# CubeSatBoard1.net
KiCad netlist of a schematic drawn in EAGLE
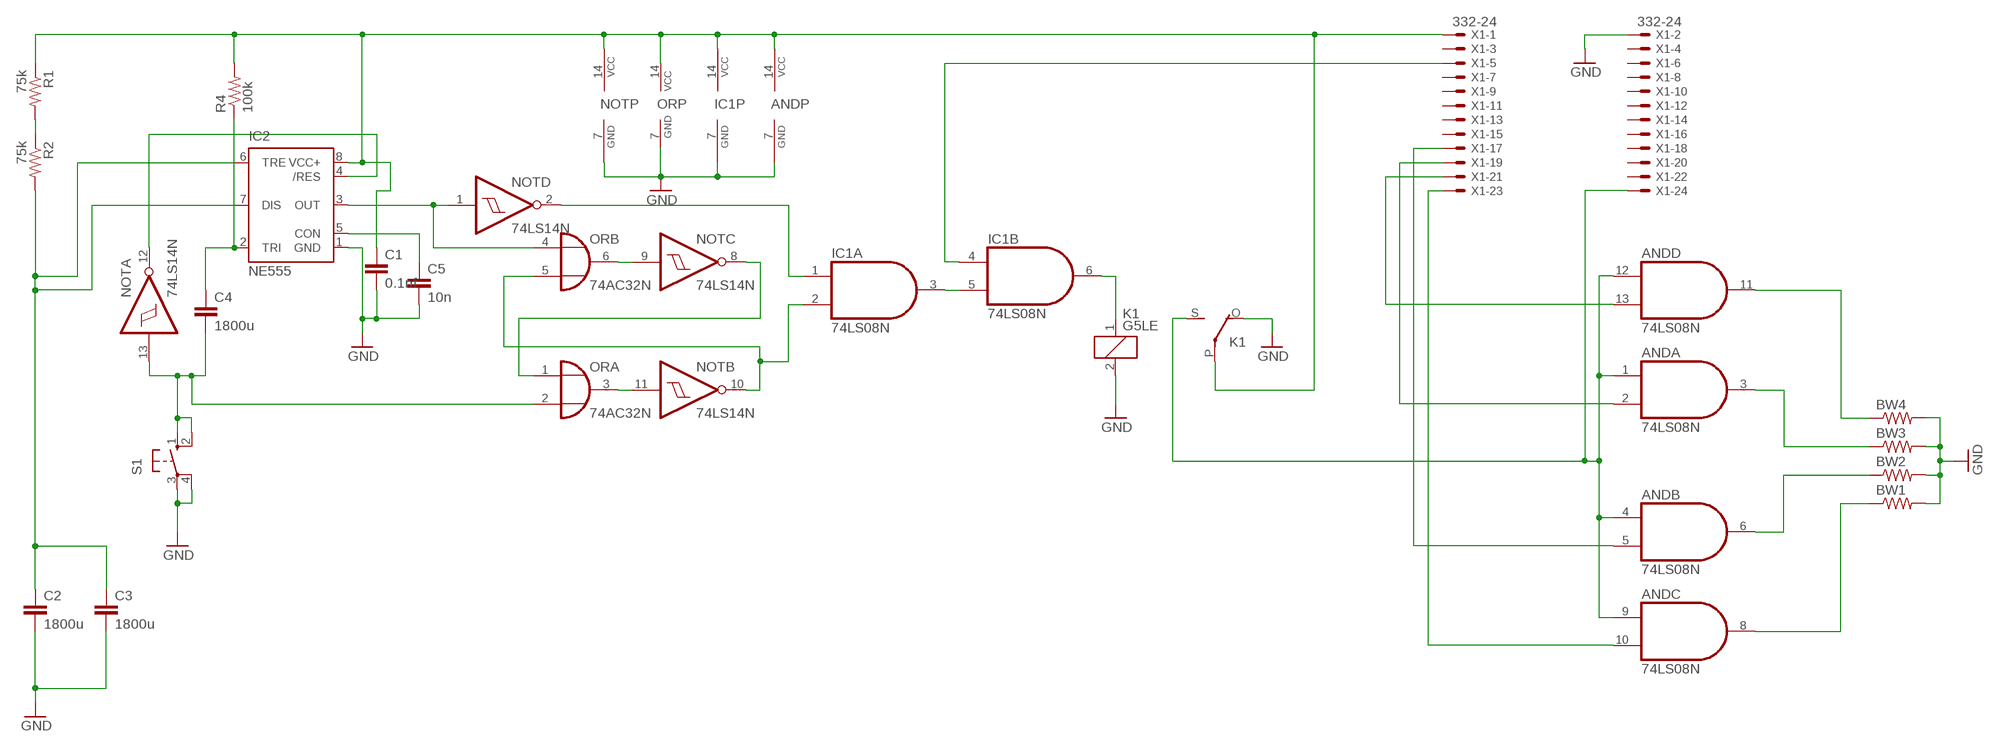
[diagram p0: schematic, sheet 1]

(export (version "E")
  (design (tool "Eeschema 10.0.6"))
  (components
    (comp (ref "AND")
      (value "74LS08N")
      (footprint "eagle-import:DIL14")
      (libsource (lib "eagle-import") (part "7408NLS"))
    )
    (comp (ref "BW1")
      (value "R-US_0309/10")
      (footprint "eagle-import:0309_10")
      (libsource (lib "eagle-import") (part "R-US_0309/10"))
    )
    (comp (ref "BW2")
      (value "R-US_0309/10")
      (footprint "eagle-import:0309_10")
      (libsource (lib "eagle-import") (part "R-US_0309/10"))
    )
    (comp (ref "BW3")
      (value "R-US_0309/10")
      (footprint "eagle-import:0309_10")
      (libsource (lib "eagle-import") (part "R-US_0309/10"))
    )
    (comp (ref "BW4")
      (value "R-US_0309/10")
      (footprint "eagle-import:0309_10")
      (libsource (lib "eagle-import") (part "R-US_0309/10"))
    )
    (comp (ref "C1")
      (value "0.1nf")
      (footprint "eagle-import:C5B3")
      (libsource (lib "eagle-import") (part "C5/3"))
    )
    (comp (ref "C2")
      (value "1800u")
      (footprint "eagle-import:C5B3")
      (libsource (lib "eagle-import") (part "C5/3"))
    )
    (comp (ref "C3")
      (value "1800u")
      (footprint "eagle-import:C5B3")
      (libsource (lib "eagle-import") (part "C5/3"))
    )
    (comp (ref "C4")
      (value "1800u")
      (footprint "eagle-import:C5B3")
      (libsource (lib "eagle-import") (part "C5/3"))
    )
    (comp (ref "C5")
      (value "10n")
      (footprint "eagle-import:C5B3")
      (libsource (lib "eagle-import") (part "C5/3"))
    )
    (comp (ref "IC1")
      (value "74LS08N")
      (footprint "eagle-import:DIL14")
      (libsource (lib "eagle-import") (part "7408NLS"))
    )
    (comp (ref "IC2")
      (value "NE555")
      (footprint "eagle-import:DIL-08")
      (fields (field (name "MF") "Arrow Electronics") (field (name "MPN") "NE555N"))
      (libsource (lib "eagle-import") (part "NE555"))
    )
    (comp (ref "K1")
      (value "G5LE")
      (footprint "eagle-import:G5LE")
      (libsource (lib "eagle-import") (part "G5LE"))
    )
    (comp (ref "NOT")
      (value "74LS14N")
      (footprint "eagle-import:DIL14")
      (libsource (lib "eagle-import") (part "7414NLS"))
    )
    (comp (ref "OR")
      (value "74AC32N")
      (footprint "eagle-import:DIL14")
      (libsource (lib "eagle-import") (part "7432NAC"))
    )
    (comp (ref "R1")
      (value "75k")
      (footprint "eagle-import:0309_10")
      (libsource (lib "eagle-import") (part "R-US_0309/10"))
    )
    (comp (ref "R2")
      (value "75k")
      (footprint "eagle-import:0309_10")
      (libsource (lib "eagle-import") (part "R-US_0309/10"))
    )
    (comp (ref "R4")
      (value "100k")
      (footprint "eagle-import:0309_10")
      (libsource (lib "eagle-import") (part "R-US_0309/10"))
    )
    (comp (ref "S1")
      (value "10-XX")
      (footprint "eagle-import:B3F-10XX")
      (fields (field (name "MPN") "B3F-1000"))
      (libsource (lib "eagle-import") (part "10-XX"))
    )
    (comp (ref "X1")
      (value "332-24")
      (footprint "eagle-import:332-24")
      (libsource (lib "eagle-import") (part "332-24"))
    )
  )
  (nets
    (net (code "1") (name "GND") (class "Default")
      (node (ref "AND") (pin "7") (pinfunction "GND_7") (pintype "power_in"))
      (node (ref "BW1") (pin "2") (pinfunction "2_2") (pintype "passive"))
      (node (ref "BW2") (pin "2") (pinfunction "2_2") (pintype "passive"))
      (node (ref "BW3") (pin "2") (pinfunction "2_2") (pintype "passive"))
      (node (ref "BW4") (pin "2") (pinfunction "2_2") (pintype "passive"))
      (node (ref "C1") (pin "2") (pinfunction "2_2") (pintype "passive"))
      (node (ref "C2") (pin "2") (pinfunction "2_2") (pintype "passive"))
      (node (ref "C3") (pin "2") (pinfunction "2_2") (pintype "passive"))
      (node (ref "C5") (pin "2") (pinfunction "2_2") (pintype "passive"))
      (node (ref "IC1") (pin "7") (pinfunction "GND_7") (pintype "power_in"))
      (node (ref "IC2") (pin "1") (pinfunction "GND_1") (pintype "power_in"))
      (node (ref "K1") (pin "2") (pinfunction "2_2") (pintype "passive"))
      (node (ref "K1") (pin "O") (pinfunction "O_O") (pintype "passive"))
      (node (ref "NOT") (pin "7") (pinfunction "GND_7") (pintype "power_in"))
      (node (ref "OR") (pin "7") (pinfunction "GND_7") (pintype "power_in"))
      (node (ref "S1") (pin "3") (pinfunction "P_3") (pintype "passive"))
      (node (ref "S1") (pin "4") (pinfunction "P1_4") (pintype "passive"))
      (node (ref "X1") (pin "2") (pinfunction "S_2") (pintype "passive"))
    )
    (net (code "2") (name "Net-(ANDA-I0)") (class "Default")
      (node (ref "AND") (pin "1") (pinfunction "I0_1") (pintype "input"))
      (node (ref "AND") (pin "12") (pinfunction "I0_12") (pintype "input"))
      (node (ref "AND") (pin "4") (pinfunction "I0_4") (pintype "input"))
      (node (ref "AND") (pin "9") (pinfunction "I0_9") (pintype "input"))
      (node (ref "K1") (pin "S") (pinfunction "S_S") (pintype "passive"))
      (node (ref "X1") (pin "24") (pinfunction "S_24") (pintype "passive"))
    )
    (net (code "3") (name "Net-(ANDA-I1)") (class "Default")
      (node (ref "AND") (pin "2") (pinfunction "I1_2") (pintype "input"))
      (node (ref "X1") (pin "19") (pinfunction "S_19") (pintype "passive"))
    )
    (net (code "4") (name "Net-(ANDA-O)") (class "Default")
      (node (ref "AND") (pin "3") (pinfunction "O_3") (pintype "output"))
      (node (ref "BW3") (pin "1") (pinfunction "1_1") (pintype "passive"))
    )
    (net (code "5") (name "Net-(ANDB-I1)") (class "Default")
      (node (ref "AND") (pin "5") (pinfunction "I1_5") (pintype "input"))
      (node (ref "X1") (pin "17") (pinfunction "S_17") (pintype "passive"))
    )
    (net (code "6") (name "Net-(ANDB-O)") (class "Default")
      (node (ref "AND") (pin "6") (pinfunction "O_6") (pintype "output"))
      (node (ref "BW2") (pin "1") (pinfunction "1_1") (pintype "passive"))
    )
    (net (code "7") (name "Net-(ANDC-I1)") (class "Default")
      (node (ref "AND") (pin "10") (pinfunction "I1_10") (pintype "input"))
      (node (ref "X1") (pin "23") (pinfunction "S_23") (pintype "passive"))
    )
    (net (code "8") (name "Net-(ANDC-O)") (class "Default")
      (node (ref "AND") (pin "8") (pinfunction "O_8") (pintype "output"))
      (node (ref "BW1") (pin "1") (pinfunction "1_1") (pintype "passive"))
    )
    (net (code "9") (name "Net-(ANDD-I1)") (class "Default")
      (node (ref "AND") (pin "13") (pinfunction "I1_13") (pintype "input"))
      (node (ref "X1") (pin "21") (pinfunction "S_21") (pintype "passive"))
    )
    (net (code "10") (name "Net-(ANDD-O)") (class "Default")
      (node (ref "AND") (pin "11") (pinfunction "O_11") (pintype "output"))
      (node (ref "BW4") (pin "1") (pinfunction "1_1") (pintype "passive"))
    )
    (net (code "11") (name "Net-(ANDE-VCC)") (class "Default")
      (node (ref "AND") (pin "14") (pinfunction "VCC_14") (pintype "power_in"))
      (node (ref "C1") (pin "1") (pinfunction "1_1") (pintype "passive"))
      (node (ref "IC1") (pin "14") (pinfunction "VCC_14") (pintype "power_in"))
      (node (ref "IC2") (pin "8") (pinfunction "VCC+_8") (pintype "power_in"))
      (node (ref "K1") (pin "P") (pinfunction "P_P") (pintype "passive"))
      (node (ref "NOT") (pin "14") (pinfunction "VCC_14") (pintype "power_in"))
      (node (ref "OR") (pin "14") (pinfunction "VCC_14") (pintype "power_in"))
      (node (ref "R1") (pin "1") (pinfunction "1_1") (pintype "passive"))
      (node (ref "R4") (pin "2") (pinfunction "2_2") (pintype "passive"))
      (node (ref "X1") (pin "1") (pinfunction "S_1") (pintype "passive"))
    )
    (net (code "12") (name "Net-(IC1A-I0)") (class "Default")
      (node (ref "IC1") (pin "1") (pinfunction "I0_1") (pintype "input"))
      (node (ref "NOT") (pin "2") (pinfunction "O_2") (pintype "output"))
    )
    (net (code "13") (name "Net-(IC1A-I1)") (class "Default")
      (node (ref "IC1") (pin "2") (pinfunction "I1_2") (pintype "input"))
      (node (ref "NOT") (pin "10") (pinfunction "O_10") (pintype "output"))
      (node (ref "OR") (pin "5") (pinfunction "I1_5") (pintype "input"))
    )
    (net (code "14") (name "Net-(IC1A-O)") (class "Default")
      (node (ref "IC1") (pin "3") (pinfunction "O_3") (pintype "output"))
      (node (ref "IC1") (pin "5") (pinfunction "I1_5") (pintype "input"))
    )
    (net (code "15") (name "Net-(IC1B-I0)") (class "Default")
      (node (ref "IC1") (pin "4") (pinfunction "I0_4") (pintype "input"))
      (node (ref "X1") (pin "5") (pinfunction "S_5") (pintype "passive"))
    )
    (net (code "16") (name "Net-(IC1B-O)") (class "Default")
      (node (ref "IC1") (pin "6") (pinfunction "O_6") (pintype "output"))
      (node (ref "K1") (pin "1") (pinfunction "1_1") (pintype "passive"))
    )
    (net (code "17") (name "Net-(IC2-CON)") (class "Default")
      (node (ref "C5") (pin "1") (pinfunction "1_1") (pintype "passive"))
      (node (ref "IC2") (pin "5") (pinfunction "CON_5") (pintype "input"))
    )
    (net (code "18") (name "Net-(IC2-DIS)") (class "Default")
      (node (ref "C2") (pin "1") (pinfunction "1_1") (pintype "passive"))
      (node (ref "C3") (pin "1") (pinfunction "1_1") (pintype "passive"))
      (node (ref "IC2") (pin "6") (pinfunction "TRE_6") (pintype "input"))
      (node (ref "IC2") (pin "7") (pinfunction "DIS_7") (pintype "input"))
      (node (ref "R2") (pin "2") (pinfunction "2_2") (pintype "passive"))
    )
    (net (code "19") (name "Net-(IC2-OUT)") (class "Default")
      (node (ref "IC2") (pin "3") (pinfunction "OUT_3") (pintype "output"))
      (node (ref "NOT") (pin "1") (pinfunction "I_1") (pintype "input"))
      (node (ref "OR") (pin "4") (pinfunction "I0_4") (pintype "input"))
    )
    (net (code "20") (name "Net-(IC2-TRI)") (class "Default")
      (node (ref "C4") (pin "1") (pinfunction "1_1") (pintype "passive"))
      (node (ref "IC2") (pin "2") (pinfunction "TRI_2") (pintype "input"))
      (node (ref "R4") (pin "1") (pinfunction "1_1") (pintype "passive"))
    )
    (net (code "21") (name "Net-(IC2-{slash}RES)") (class "Default")
      (node (ref "IC2") (pin "4") (pinfunction "/RES_4") (pintype "input"))
      (node (ref "NOT") (pin "12") (pinfunction "O_12") (pintype "output"))
    )
    (net (code "22") (name "Net-(NOTA-I)") (class "Default")
      (node (ref "C4") (pin "2") (pinfunction "2_2") (pintype "passive"))
      (node (ref "NOT") (pin "13") (pinfunction "I_13") (pintype "input"))
      (node (ref "OR") (pin "2") (pinfunction "I1_2") (pintype "input"))
      (node (ref "S1") (pin "1") (pinfunction "S_1") (pintype "passive"))
      (node (ref "S1") (pin "2") (pinfunction "S1_2") (pintype "passive"))
    )
    (net (code "23") (name "Net-(NOTB-I)") (class "Default")
      (node (ref "NOT") (pin "11") (pinfunction "I_11") (pintype "input"))
      (node (ref "OR") (pin "3") (pinfunction "O_3") (pintype "output"))
    )
    (net (code "24") (name "Net-(NOTC-I)") (class "Default")
      (node (ref "NOT") (pin "9") (pinfunction "I_9") (pintype "input"))
      (node (ref "OR") (pin "6") (pinfunction "O_6") (pintype "output"))
    )
    (net (code "25") (name "Net-(NOTC-O)") (class "Default")
      (node (ref "NOT") (pin "8") (pinfunction "O_8") (pintype "output"))
      (node (ref "OR") (pin "1") (pinfunction "I0_1") (pintype "input"))
    )
    (net (code "26") (name "Net-(R1-Pad2)") (class "Default")
      (node (ref "R1") (pin "2") (pinfunction "2_2") (pintype "passive"))
      (node (ref "R2") (pin "1") (pinfunction "1_1") (pintype "passive"))
    )
    (net (code "27") (name "unconnected-(X1B-S-Pad10)") (class "Default")
      (node (ref "X1") (pin "10") (pinfunction "S_10") (pintype "passive"))
    )
    (net (code "28") (name "unconnected-(X1C-S-Pad11)") (class "Default")
      (node (ref "X1") (pin "11") (pinfunction "S_11") (pintype "passive"))
    )
    (net (code "29") (name "unconnected-(X1D-S-Pad12)") (class "Default")
      (node (ref "X1") (pin "12") (pinfunction "S_12") (pintype "passive"))
    )
    (net (code "30") (name "unconnected-(X1E-S-Pad13)") (class "Default")
      (node (ref "X1") (pin "13") (pinfunction "S_13") (pintype "passive"))
    )
    (net (code "31") (name "unconnected-(X1F-S-Pad14)") (class "Default")
      (node (ref "X1") (pin "14") (pinfunction "S_14") (pintype "passive"))
    )
    (net (code "32") (name "unconnected-(X1G-S-Pad15)") (class "Default")
      (node (ref "X1") (pin "15") (pinfunction "S_15") (pintype "passive"))
    )
    (net (code "33") (name "unconnected-(X1H-S-Pad16)") (class "Default")
      (node (ref "X1") (pin "16") (pinfunction "S_16") (pintype "passive"))
    )
    (net (code "34") (name "unconnected-(X1J-S-Pad18)") (class "Default")
      (node (ref "X1") (pin "18") (pinfunction "S_18") (pintype "passive"))
    )
    (net (code "35") (name "unconnected-(X1M-S-Pad20)") (class "Default")
      (node (ref "X1") (pin "20") (pinfunction "S_20") (pintype "passive"))
    )
    (net (code "36") (name "unconnected-(X1O-S-Pad22)") (class "Default")
      (node (ref "X1") (pin "22") (pinfunction "S_22") (pintype "passive"))
    )
    (net (code "37") (name "unconnected-(X1R-S-Pad3)") (class "Default")
      (node (ref "X1") (pin "3") (pinfunction "S_3") (pintype "passive"))
    )
    (net (code "38") (name "unconnected-(X1S-S-Pad4)") (class "Default")
      (node (ref "X1") (pin "4") (pinfunction "S_4") (pintype "passive"))
    )
    (net (code "39") (name "unconnected-(X1U-S-Pad6)") (class "Default")
      (node (ref "X1") (pin "6") (pinfunction "S_6") (pintype "passive"))
    )
    (net (code "40") (name "unconnected-(X1V-S-Pad7)") (class "Default")
      (node (ref "X1") (pin "7") (pinfunction "S_7") (pintype "passive"))
    )
    (net (code "41") (name "unconnected-(X1W-S-Pad8)") (class "Default")
      (node (ref "X1") (pin "8") (pinfunction "S_8") (pintype "passive"))
    )
    (net (code "42") (name "unconnected-(X1X-S-Pad9)") (class "Default")
      (node (ref "X1") (pin "9") (pinfunction "S_9") (pintype "passive"))
    )
  )
)
